# MCU.net
KiCad netlist of a schematic drawn in Altium Designer
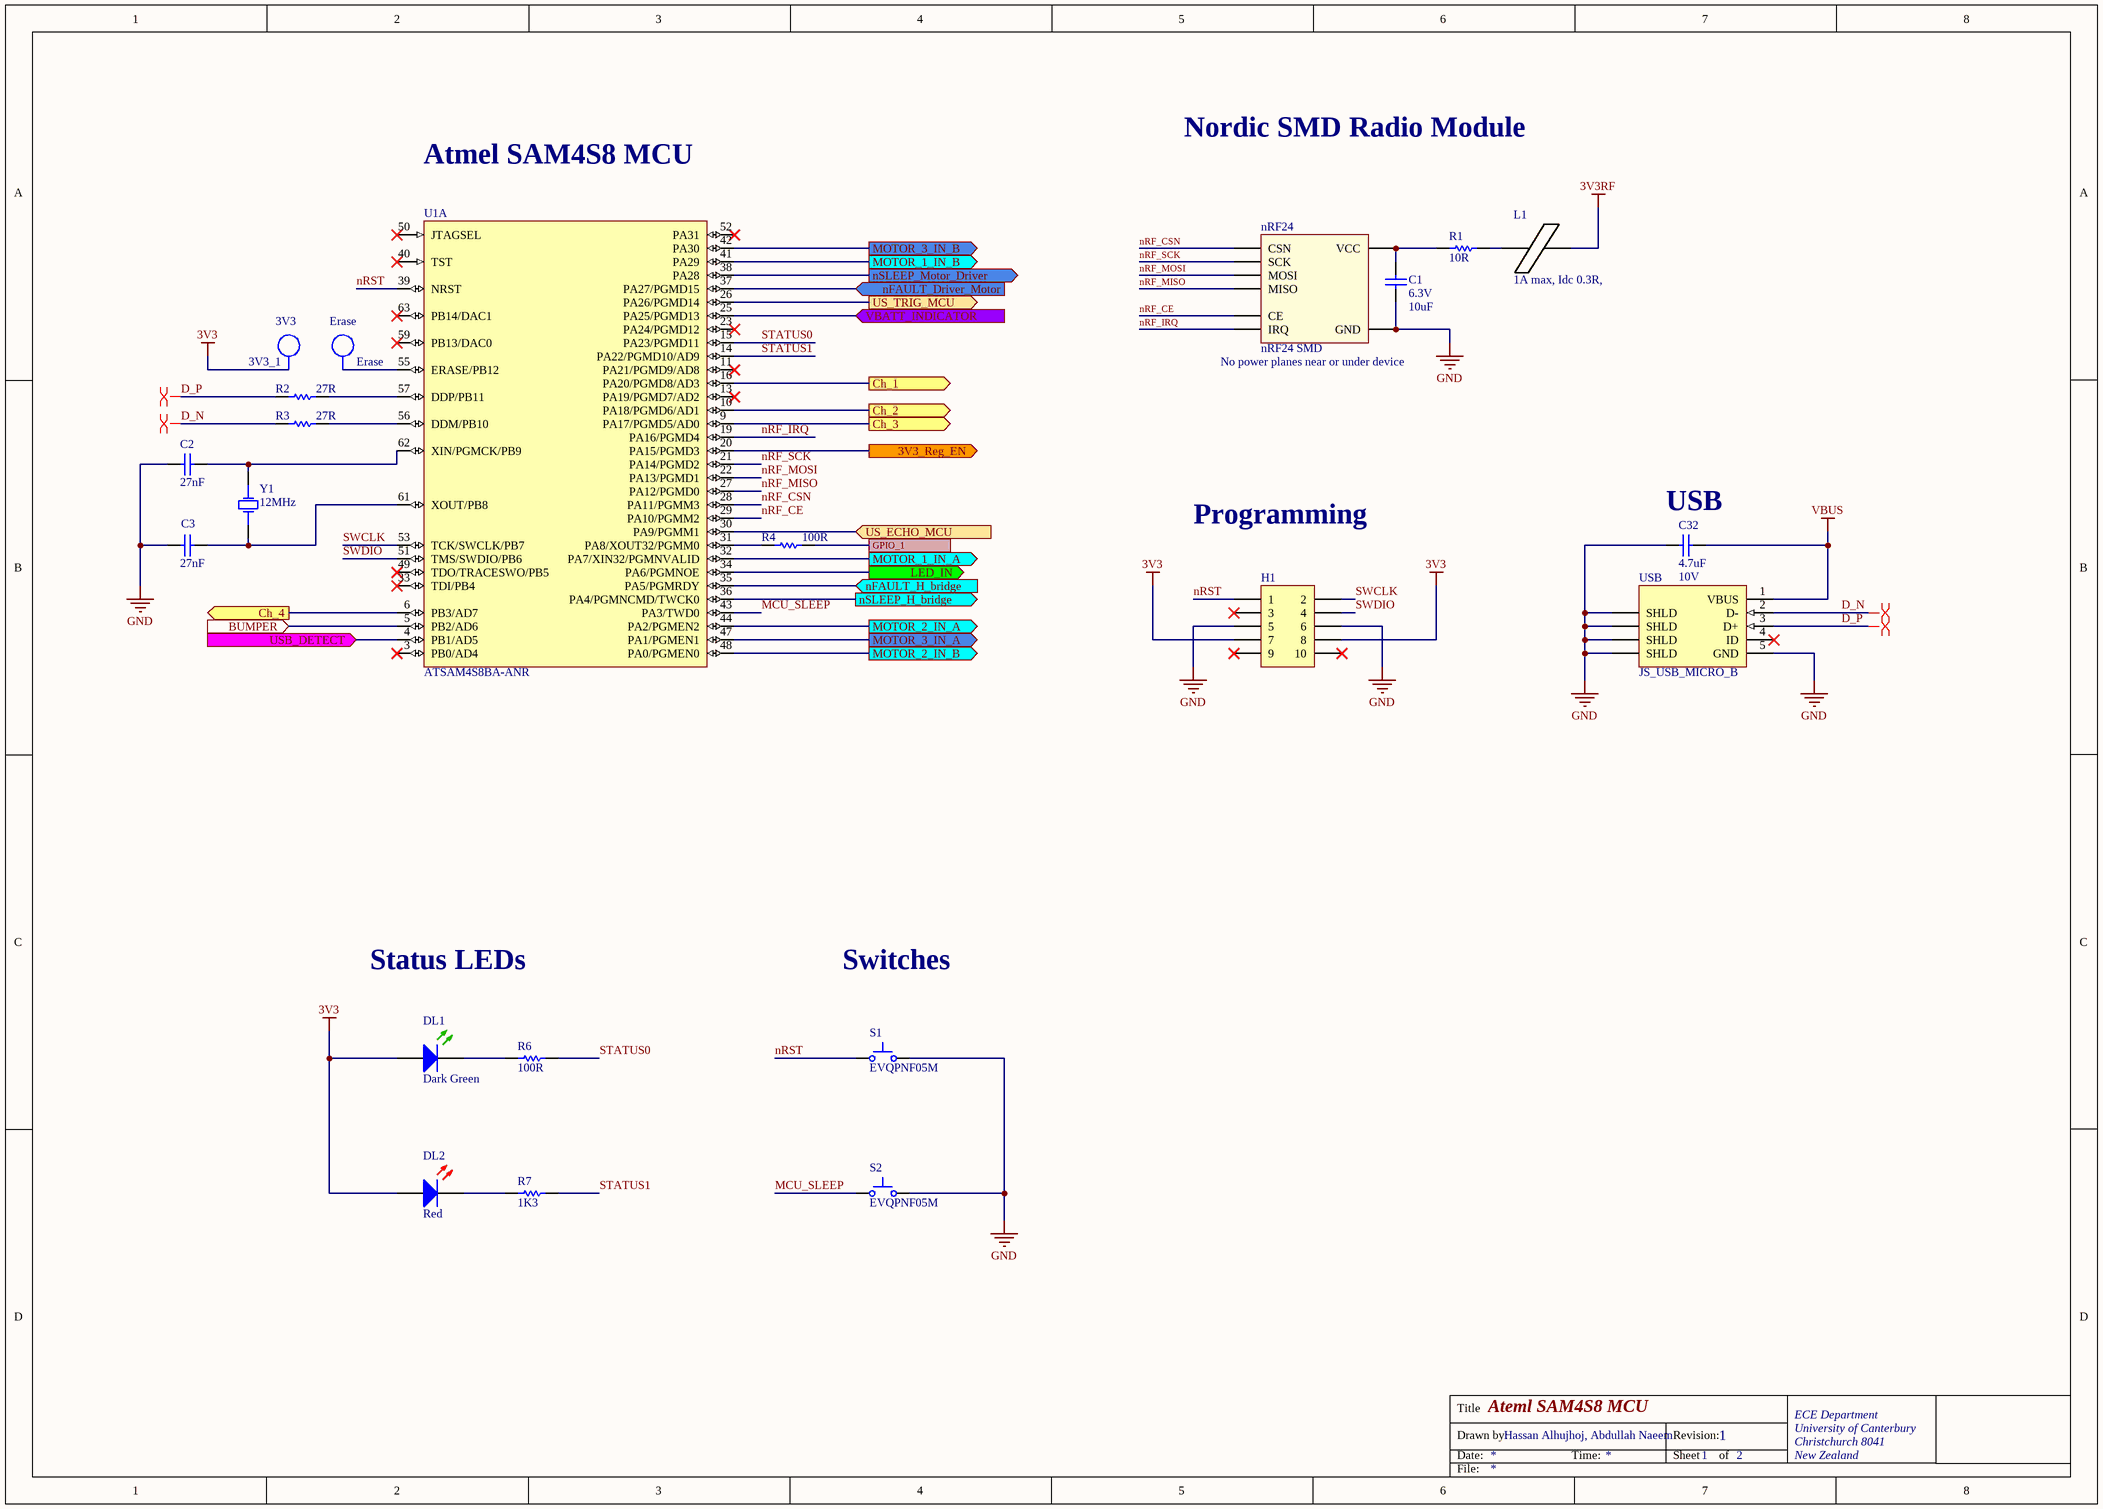
[diagram p0: MCU.SchDoc]

(export (version "E")
  (design (tool "Eeschema 10.0.6"))
  (components
    (comp (ref "3V3_1")
      (value "TP")
      (footprint "TP_1206")
      (description "Test-Point 3.3x1.6x2.1mm SMD")
      (fields
        (field (name "MANUFACTURER") "Harwin Inc")
        (field (name "MANUFACTURER PART NUMBER") "S1751-46R")
      )
      (libsource (lib "ECE AD19Components_19V1") (part "TP_1206"))
    )
    (comp (ref "C1")
      (value "10uF")
      (footprint "CAPC1608L")
      (description "CAP CER 10UF X5R +-20% 6V3 0603")
      (fields (field (name "VOLTAGE - RATED") "6.3V"))
      (libsource (lib "ECE AD19Components_19V1") (part "CC_10uF_0603"))
    )
    (comp (ref "C2")
      (value "27nF")
      (footprint "CAPC1608L")
      (description "CAP CER 27nF X7R +-10% 50V 0603")
      (libsource (lib "ECE AD19Components_19V1") (part "CC_27nF_0603"))
    )
    (comp (ref "C3")
      (value "27nF")
      (footprint "CAPC1608L")
      (description "CAP CER 27nF X7R +-10% 50V 0603")
      (libsource (lib "ECE AD19Components_19V1") (part "CC_27nF_0603"))
    )
    (comp (ref "C32")
      (value "4.7uF")
      (footprint "CAPC1608N")
      (description "CAP CER 4.7uF X5R +-20%  10V 0603")
      (fields (field (name "MAX VOLTAGE") "10V"))
      (libsource (lib "ECE AD19Components_19V1") (part "CC_4.7uF_0603"))
    )
    (comp (ref "DL1")
      (value "Dark Green")
      (footprint "WL-SMCW0603")
      (description "LED Dk Green 430mcd 0603 SMD")
      (fields
        (field (name "MANUFACTURER") "WURTH ELEKTRONIK")
        (field (name "MANUFACTURER PART NUMBER") "150060GS75000")
        (field (name "LED COLOUR") "Dark Green")
      )
      (libsource (lib "ECE AD19Components_19V1") (part "DL_150060GS75000"))
    )
    (comp (ref "DL2")
      (value "Red")
      (footprint "WL-SMCW0603")
      (description "LED Red 250mcd 0603 SMD")
      (fields
        (field (name "MANUFACTURER") "WURTH ELEKTRONIK")
        (field (name "MANUFACTURER PART NUMBER") "150060RS75000")
        (field (name "LED COLOUR") "Red")
      )
      (libsource (lib "ECE AD19Components_19V1") (part "DL_150060RS75000"))
    )
    (comp (ref "Erase")
      (value "TP")
      (footprint "TP_1206")
      (description "Test-Point 3.3x1.6x2.1mm SMD")
      (fields
        (field (name "MANUFACTURER") "Harwin Inc")
        (field (name "MANUFACTURER PART NUMBER") "S1751-46R")
      )
      (libsource (lib "ECE AD19Components_19V1") (part "TP_1206"))
    )
    (comp (ref "H1")
      (value "Header 5X2 Vert")
      (footprint "IDC2.54-V10D")
      (description "IDC Header, 2,54mm, 10-Pin, Vert")
      (libsource (lib "ECE AD19Components_19V1") (part "JA_HDR_IDC_5X2_VERT"))
    )
    (comp (ref "L1")
      (value "1A max, Idc 0.3R,")
      (footprint "INDC3216L")
      (description "Ferrite Bead, Rdc 0.3R, Z100MHZ 600R, Imax 1A, SMD 1206")
      (fields
        (field (name "MANUFACTURER") "FAIR-RITE")
        (field (name "MANUFACTURER PART NUMBER") "2512066017Y1")
      )
      (libsource (lib "ECE AD19Components_19V1") (part "IN_Ferrite-Bead"))
    )
    (comp (ref "nRF24")
      (value "nRF24 SMD")
      (footprint "NRF24")
      (description "nRF24 SMD Module")
      (fields (field (name "WARNING") "No power planes near or under device"))
      (libsource (lib "ENCE461AD19_19V2") (part "NRF24"))
    )
    (comp (ref "R1")
      (value "10R")
      (footprint "RESC1608L")
      (description "RES 10 OHM 1/10W 5% 0603 SMD")
      (libsource (lib "ECE AD19Components_19V1") (part "RS_10R"))
    )
    (comp (ref "R2")
      (value "27R")
      (footprint "RESC1608L")
      (description "RES 27 OHM 1/10W 5% 0603 SMD")
      (libsource (lib "ECE AD19Components_19V1") (part "RS_27R"))
    )
    (comp (ref "R3")
      (value "27R")
      (footprint "RESC1608L")
      (description "RES 27 OHM 1/10W 5% 0603 SMD")
      (libsource (lib "ECE AD19Components_19V1") (part "RS_27R"))
    )
    (comp (ref "R4")
      (value "100R")
      (footprint "RESC1608L")
      (description "RES 100 OHM 1/10W 5% 0603 SMD")
      (libsource (lib "ECE AD19Components_19V1") (part "RS_100R"))
    )
    (comp (ref "R6")
      (value "100R")
      (footprint "RESC1608L")
      (description "RES 100 OHM 1/10W 5% 0603 SMD")
      (libsource (lib "ECE AD19Components_19V1") (part "RS_100R"))
    )
    (comp (ref "R7")
      (value "1K3")
      (footprint "RESC1608L")
      (description "RES 1.3K OHM 1/10W 5% 0603 SMD")
      (libsource (lib "ECE AD19Components_19V1") (part "RS_1K3"))
    )
    (comp (ref "S1")
      (value "EVQPNF05M")
      (footprint "EVQPNF05M")
      (description "Panasonic 6 x 3.5mm SMD Light Touch Switch Type SMD")
      (fields (field (name "MANUFACTURER") "Panasonic"))
      (libsource (lib "ECE AD19Components_19V1") (part "WS_EVQPNF05M"))
    )
    (comp (ref "S2")
      (value "EVQPNF05M")
      (footprint "EVQPNF05M")
      (description "Panasonic 6 x 3.5mm SMD Light Touch Switch Type SMD")
      (fields (field (name "MANUFACTURER") "Panasonic"))
      (libsource (lib "ECE AD19Components_19V1") (part "WS_EVQPNF05M"))
    )
    (comp (ref "U1")
      (value "ATSAM4S8BA-ANR")
      (footprint "LQFP64_L")
      (description "IC MCU 32BIT 512KB FLASH 64LQFP")
      (fields (field (name "MANUFACTURER") "Atmel"))
      (libsource (lib "ECE AD19Components_19V1") (part "SE_ATSAM4S16BA-MU"))
    )
    (comp (ref "USB")
      (value "JS_USB_MICRO_B")
      (footprint "FCI_USB_10118194-0001LF")
      (description "CONN USB MICRO B RECPT SMT R/A")
      (fields (field (name "MANUFACTURER") "FCI") (field (name "MANUFACTURER PART NUMBER") "10118194-0001LF"))
      (libsource (lib "ECE AD19Components_19V1") (part "JS_USB_MICRO_B_SMT"))
    )
    (comp (ref "Y1")
      (value "12MHz")
      (footprint "6.0X3.5-4")
      (description "CRYSTAL 12MHZ 18PF 6X3.5mm SMD")
      (fields
        (field (name "MANUFACTURER") "CTS-Frequency Controls")
        (field (name "MANUFACTURER PART NUMBER") "406C35D12M00000")
        (field (name "FREQUENCY") "12MHz")
      )
      (libsource (lib "ECE AD19Components_19V1") (part "XT_CRYSTAL_12MHz_18pF"))
    )
  )
  (nets
    (net (code "1") (name "/3V3_Reg_EN") (class "Default")
      (node (ref "U1") (pin "20") (pinfunction "PA15/PGMD3_20") (pintype "bidirectional"))
    )
    (net (code "2") (name "/BUMPER") (class "Default")
      (node (ref "U1") (pin "5") (pinfunction "PB2/AD6_5") (pintype "bidirectional"))
    )
    (net (code "3") (name "/Ch_1") (class "Default")
      (node (ref "U1") (pin "16") (pinfunction "PA20/PGMD8/AD3_16") (pintype "bidirectional"))
    )
    (net (code "4") (name "/Ch_2") (class "Default")
      (node (ref "U1") (pin "10") (pinfunction "PA18/PGMD6/AD1_10") (pintype "bidirectional"))
    )
    (net (code "5") (name "/Ch_3") (class "Default")
      (node (ref "U1") (pin "9") (pinfunction "PA17/PGMD5/AD0_9") (pintype "bidirectional"))
    )
    (net (code "6") (name "/Ch_4") (class "Default")
      (node (ref "U1") (pin "6") (pinfunction "PB3/AD7_6") (pintype "bidirectional"))
    )
    (net (code "7") (name "/D_N") (class "Default")
      (node (ref "R3") (pin "1") (pinfunction "1_1") (pintype "passive"))
      (node (ref "USB") (pin "2") (pinfunction "D-_2") (pintype "input"))
    )
    (net (code "8") (name "/D_P") (class "Default")
      (node (ref "R2") (pin "1") (pinfunction "1_1") (pintype "passive"))
      (node (ref "USB") (pin "3") (pinfunction "D+_3") (pintype "input"))
    )
    (net (code "9") (name "/GPIO_1") (class "Default")
      (node (ref "R4") (pin "2") (pinfunction "2_2") (pintype "passive"))
    )
    (net (code "10") (name "/LED_IN") (class "Default")
      (node (ref "U1") (pin "34") (pinfunction "PA6/PGMNOE_34") (pintype "bidirectional"))
    )
    (net (code "11") (name "/MCU_SLEEP") (class "Default")
      (node (ref "S2") (pin "1") (pintype "passive"))
      (node (ref "U1") (pin "43") (pinfunction "PA3/TWD0_43") (pintype "bidirectional"))
    )
    (net (code "12") (name "/MOTOR_1_IN_A") (class "Default")
      (node (ref "U1") (pin "32") (pinfunction "PA7/XIN32/PGMNVALID_32") (pintype "bidirectional"))
    )
    (net (code "13") (name "/MOTOR_1_IN_B") (class "Default")
      (node (ref "U1") (pin "41") (pinfunction "PA29_41") (pintype "bidirectional"))
    )
    (net (code "14") (name "/MOTOR_2_IN_A") (class "Default")
      (node (ref "U1") (pin "44") (pinfunction "PA2/PGMEN2_44") (pintype "bidirectional"))
    )
    (net (code "15") (name "/MOTOR_2_IN_B") (class "Default")
      (node (ref "U1") (pin "48") (pinfunction "PA0/PGMEN0_48") (pintype "bidirectional"))
    )
    (net (code "16") (name "/MOTOR_3_IN_A") (class "Default")
      (node (ref "U1") (pin "47") (pinfunction "PA1/PGMEN1_47") (pintype "bidirectional"))
    )
    (net (code "17") (name "/MOTOR_3_IN_B") (class "Default")
      (node (ref "U1") (pin "42") (pinfunction "PA30_42") (pintype "bidirectional"))
    )
    (net (code "18") (name "/STATUS0") (class "Default")
      (node (ref "R6") (pin "2") (pinfunction "2_2") (pintype "passive"))
      (node (ref "U1") (pin "15") (pinfunction "PA23/PGMD11_15") (pintype "bidirectional"))
    )
    (net (code "19") (name "/STATUS1") (class "Default")
      (node (ref "R7") (pin "2") (pinfunction "2_2") (pintype "passive"))
      (node (ref "U1") (pin "14") (pinfunction "PA22/PGMD10/AD9_14") (pintype "bidirectional"))
    )
    (net (code "20") (name "/SWCLK") (class "Default")
      (node (ref "H1") (pin "2") (pinfunction "2_2") (pintype "passive"))
      (node (ref "U1") (pin "53") (pinfunction "TCK/SWCLK/PB7_53") (pintype "bidirectional"))
    )
    (net (code "21") (name "/SWDIO") (class "Default")
      (node (ref "H1") (pin "4") (pinfunction "4_4") (pintype "passive"))
      (node (ref "U1") (pin "51") (pinfunction "TMS/SWDIO/PB6_51") (pintype "bidirectional"))
    )
    (net (code "22") (name "/USB_DETECT") (class "Default")
      (node (ref "U1") (pin "4") (pinfunction "PB1/AD5_4") (pintype "bidirectional"))
    )
    (net (code "23") (name "/US_ECHO_MCU") (class "Default")
      (node (ref "U1") (pin "30") (pinfunction "PA9/PGMM1_30") (pintype "bidirectional"))
    )
    (net (code "24") (name "/US_TRIG_MCU") (class "Default")
      (node (ref "U1") (pin "26") (pinfunction "PA26/PGMD14_26") (pintype "bidirectional"))
    )
    (net (code "25") (name "/VBATT_INDICATOR") (class "Default")
      (node (ref "U1") (pin "25") (pinfunction "PA25/PGMD13_25") (pintype "bidirectional"))
    )
    (net (code "26") (name "/nFAULT_Driver_Motor") (class "Default")
      (node (ref "U1") (pin "37") (pinfunction "PA27/PGMD15_37") (pintype "bidirectional"))
    )
    (net (code "27") (name "/nFAULT_H_bridge") (class "Default")
      (node (ref "U1") (pin "35") (pinfunction "PA5/PGMRDY_35") (pintype "bidirectional"))
    )
    (net (code "28") (name "/nRF_CE") (class "Default")
      (node (ref "U1") (pin "29") (pinfunction "PA10/PGMM2_29") (pintype "bidirectional"))
      (node (ref "nRF24") (pin "3") (pinfunction "CE_3") (pintype "passive"))
    )
    (net (code "29") (name "/nRF_CSN") (class "Default")
      (node (ref "U1") (pin "28") (pinfunction "PA11/PGMM3_28") (pintype "bidirectional"))
      (node (ref "nRF24") (pin "4") (pinfunction "CSN_4") (pintype "passive"))
    )
    (net (code "30") (name "/nRF_IRQ") (class "Default")
      (node (ref "U1") (pin "19") (pinfunction "PA16/PGMD4_19") (pintype "bidirectional"))
      (node (ref "nRF24") (pin "8") (pinfunction "IRQ_8") (pintype "passive"))
    )
    (net (code "31") (name "/nRF_MISO") (class "Default")
      (node (ref "U1") (pin "27") (pinfunction "PA12/PGMD0_27") (pintype "bidirectional"))
      (node (ref "nRF24") (pin "7") (pinfunction "MISO_7") (pintype "passive"))
    )
    (net (code "32") (name "/nRF_MOSI") (class "Default")
      (node (ref "U1") (pin "22") (pinfunction "PA13/PGMD1_22") (pintype "bidirectional"))
      (node (ref "nRF24") (pin "6") (pinfunction "MOSI_6") (pintype "passive"))
    )
    (net (code "33") (name "/nRF_SCK") (class "Default")
      (node (ref "U1") (pin "21") (pinfunction "PA14/PGMD2_21") (pintype "bidirectional"))
      (node (ref "nRF24") (pin "5") (pinfunction "SCK_5") (pintype "passive"))
    )
    (net (code "34") (name "/nRST") (class "Default")
      (node (ref "H1") (pin "1") (pinfunction "1_1") (pintype "passive"))
      (node (ref "S1") (pin "1") (pintype "passive"))
      (node (ref "U1") (pin "39") (pinfunction "NRST_39") (pintype "bidirectional"))
    )
    (net (code "35") (name "/nSLEEP_H_bridge") (class "Default")
      (node (ref "U1") (pin "36") (pinfunction "PA4/PGMNCMD/TWCK0_36") (pintype "bidirectional"))
    )
    (net (code "36") (name "/nSLEEP_Motor_Driver") (class "Default")
      (node (ref "U1") (pin "38") (pinfunction "PA28_38") (pintype "bidirectional"))
    )
    (net (code "37") (name "3V3") (class "Default")
      (node (ref "3V3_1") (pin "1") (pinfunction "1_1") (pintype "passive"))
      (node (ref "DL1") (pin "2") (pinfunction "A_2") (pintype "passive"))
      (node (ref "DL2") (pin "2") (pinfunction "A_2") (pintype "passive"))
      (node (ref "H1") (pin "7") (pinfunction "7_7") (pintype "passive"))
      (node (ref "H1") (pin "8") (pinfunction "8_8") (pintype "passive"))
    )
    (net (code "38") (name "3V3RF") (class "Default")
      (node (ref "L1") (pin "2") (pinfunction "2_2") (pintype "passive"))
    )
    (net (code "39") (name "GND") (class "Default")
      (node (ref "C1") (pin "1") (pinfunction "1_1") (pintype "passive"))
      (node (ref "C2") (pin "1") (pinfunction "1_1") (pintype "passive"))
      (node (ref "C3") (pin "1") (pinfunction "1_1") (pintype "passive"))
      (node (ref "C32") (pin "1") (pinfunction "1_1") (pintype "passive"))
      (node (ref "H1") (pin "5") (pinfunction "5_5") (pintype "passive"))
      (node (ref "H1") (pin "6") (pinfunction "6_6") (pintype "passive"))
      (node (ref "S1") (pin "2") (pintype "passive"))
      (node (ref "S2") (pin "2") (pintype "passive"))
      (node (ref "USB") (pin "5") (pinfunction "GND_5") (pintype "passive"))
      (node (ref "USB") (pin "6") (pinfunction "SHLD_6") (pintype "passive"))
      (node (ref "nRF24") (pin "2") (pinfunction "GND_2") (pintype "passive"))
    )
    (net (code "40") (name "Net-(DL1-K)") (class "Default")
      (node (ref "DL1") (pin "1") (pinfunction "K_1") (pintype "passive"))
      (node (ref "R6") (pin "1") (pinfunction "1_1") (pintype "passive"))
    )
    (net (code "41") (name "Net-(DL2-K)") (class "Default")
      (node (ref "DL2") (pin "1") (pinfunction "K_1") (pintype "passive"))
      (node (ref "R7") (pin "1") (pinfunction "1_1") (pintype "passive"))
    )
    (net (code "42") (name "Net-(L1-Pad1)") (class "Default")
      (node (ref "L1") (pin "1") (pinfunction "1_1") (pintype "passive"))
      (node (ref "R1") (pin "2") (pinfunction "2_2") (pintype "passive"))
    )
    (net (code "43") (name "Net-(U1A-DDM{slash}PB10)") (class "Default")
      (node (ref "R3") (pin "2") (pinfunction "2_2") (pintype "passive"))
      (node (ref "U1") (pin "56") (pinfunction "DDM/PB10_56") (pintype "bidirectional"))
    )
    (net (code "44") (name "Net-(U1A-DDP{slash}PB11)") (class "Default")
      (node (ref "R2") (pin "2") (pinfunction "2_2") (pintype "passive"))
      (node (ref "U1") (pin "57") (pinfunction "DDP/PB11_57") (pintype "bidirectional"))
    )
    (net (code "45") (name "Net-(U1A-ERASE{slash}PB12)") (class "Default")
      (node (ref "Erase") (pin "1") (pinfunction "1_1") (pintype "passive"))
      (node (ref "U1") (pin "55") (pinfunction "ERASE/PB12_55") (pintype "bidirectional"))
    )
    (net (code "46") (name "Net-(U1A-PA8{slash}XOUT32{slash}PGMM0)") (class "Default")
      (node (ref "R4") (pin "1") (pinfunction "1_1") (pintype "passive"))
      (node (ref "U1") (pin "31") (pinfunction "PA8/XOUT32/PGMM0_31") (pintype "bidirectional"))
    )
    (net (code "47") (name "Net-(U1A-XIN{slash}PGMCK{slash}PB9)") (class "Default")
      (node (ref "C2") (pin "2") (pinfunction "2_2") (pintype "passive"))
      (node (ref "U1") (pin "62") (pinfunction "XIN/PGMCK/PB9_62") (pintype "bidirectional"))
      (node (ref "Y1") (pin "3") (pinfunction "OSC2_3") (pintype "passive"))
    )
    (net (code "48") (name "Net-(U1A-XOUT{slash}PB8)") (class "Default")
      (node (ref "C3") (pin "2") (pinfunction "2_2") (pintype "passive"))
      (node (ref "U1") (pin "61") (pinfunction "XOUT/PB8_61") (pintype "bidirectional"))
      (node (ref "Y1") (pin "1") (pinfunction "OSC1_1") (pintype "passive"))
    )
    (net (code "49") (name "Net-(nRF24-VCC)") (class "Default")
      (node (ref "C1") (pin "2") (pinfunction "2_2") (pintype "passive"))
      (node (ref "R1") (pin "1") (pinfunction "1_1") (pintype "passive"))
      (node (ref "nRF24") (pin "1") (pinfunction "VCC_1") (pintype "passive"))
    )
    (net (code "50") (name "VBUS") (class "Default")
      (node (ref "C32") (pin "2") (pinfunction "2_2") (pintype "passive"))
      (node (ref "USB") (pin "1") (pinfunction "VBUS_1") (pintype "power_in"))
    )
    (net (code "51") (name "unconnected-(H1-Pad3)") (class "Default")
      (node (ref "H1") (pin "3") (pinfunction "3_3") (pintype "passive+no_connect"))
    )
    (net (code "52") (name "unconnected-(H1-Pad9)") (class "Default")
      (node (ref "H1") (pin "9") (pinfunction "9_9") (pintype "passive+no_connect"))
    )
    (net (code "53") (name "unconnected-(H1-Pad10)") (class "Default")
      (node (ref "H1") (pin "10") (pinfunction "10_10") (pintype "passive+no_connect"))
    )
    (net (code "54") (name "unconnected-(U1A-JTAGSEL-Pad50)") (class "Default")
      (node (ref "U1") (pin "50") (pinfunction "JTAGSEL_50") (pintype "input+no_connect"))
    )
    (net (code "55") (name "unconnected-(U1A-PA19{slash}PGMD7{slash}AD2-Pad13)") (class "Default")
      (node (ref "U1") (pin "13") (pinfunction "PA19/PGMD7/AD2_13") (pintype "bidirectional+no_connect"))
    )
    (net (code "56") (name "unconnected-(U1A-PA21{slash}PGMD9{slash}AD8-Pad11)") (class "Default")
      (node (ref "U1") (pin "11") (pinfunction "PA21/PGMD9/AD8_11") (pintype "bidirectional+no_connect"))
    )
    (net (code "57") (name "unconnected-(U1A-PA24{slash}PGMD12-Pad23)") (class "Default")
      (node (ref "U1") (pin "23") (pinfunction "PA24/PGMD12_23") (pintype "bidirectional+no_connect"))
    )
    (net (code "58") (name "unconnected-(U1A-PA31-Pad52)") (class "Default")
      (node (ref "U1") (pin "52") (pinfunction "PA31_52") (pintype "bidirectional+no_connect"))
    )
    (net (code "59") (name "unconnected-(U1A-PB0{slash}AD4-Pad3)") (class "Default")
      (node (ref "U1") (pin "3") (pinfunction "PB0/AD4_3") (pintype "bidirectional+no_connect"))
    )
    (net (code "60") (name "unconnected-(U1A-PB13{slash}DAC0-Pad59)") (class "Default")
      (node (ref "U1") (pin "59") (pinfunction "PB13/DAC0_59") (pintype "bidirectional+no_connect"))
    )
    (net (code "61") (name "unconnected-(U1A-PB14{slash}DAC1-Pad63)") (class "Default")
      (node (ref "U1") (pin "63") (pinfunction "PB14/DAC1_63") (pintype "bidirectional+no_connect"))
    )
    (net (code "62") (name "unconnected-(U1A-TDI{slash}PB4-Pad33)") (class "Default")
      (node (ref "U1") (pin "33") (pinfunction "TDI/PB4_33") (pintype "bidirectional+no_connect"))
    )
    (net (code "63") (name "unconnected-(U1A-TDO{slash}TRACESWO{slash}PB5-Pad49)") (class "Default")
      (node (ref "U1") (pin "49") (pinfunction "TDO/TRACESWO/PB5_49") (pintype "bidirectional+no_connect"))
    )
    (net (code "64") (name "unconnected-(U1A-TST-Pad40)") (class "Default")
      (node (ref "U1") (pin "40") (pinfunction "TST_40") (pintype "input+no_connect"))
    )
    (net (code "65") (name "unconnected-(USB-ID-Pad4)") (class "Default")
      (node (ref "USB") (pin "4") (pinfunction "ID_4") (pintype "power_in+no_connect"))
    )
  )
)
